# 74LVC8T245.net
KiCad netlist of a schematic drawn in Altium Designer
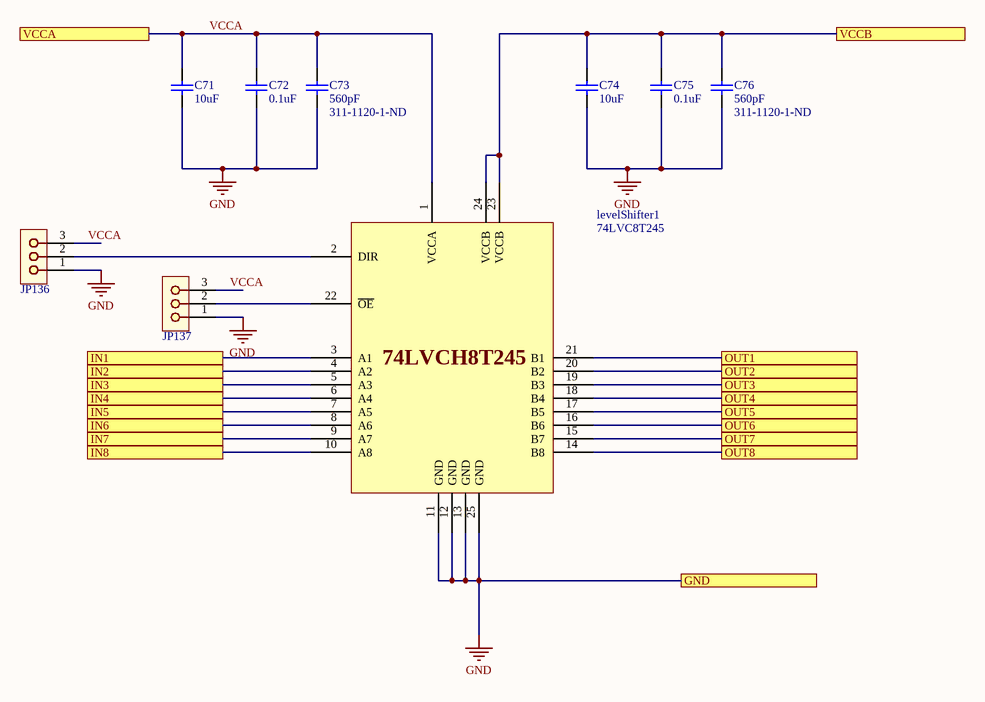
[diagram p0: 74LVC8T245.SchDoc]

(export (version "E")
  (design (tool "Eeschema 10.0.6"))
  (components
    (comp (ref "C71")
      (value "10uF")
      (footprint "CLS_Library:C0805")
      (description "Cap 10uF")
      (fields
        (field (name "MANUFACTURER") "Taiyo Yuden")
        (field (name "MANUFACTURER PART NUMBER") "UMK212SD103KD-T")
      )
      (libsource (lib "Chip1_TestBoard") (part "Cap 10uF"))
    )
    (comp (ref "C72")
      (value "0.1uF")
      (footprint "CLS_Library:C0805")
      (description "Cap 0.1uF")
      (fields
        (field (name "MANUFACTURER") "Taiyo Yuden")
        (field (name "MANUFACTURER PART NUMBER") "UMK212SD103KD-T")
      )
      (libsource (lib "Chip1_TestBoard") (part "Cap 0.1uF"))
    )
    (comp (ref "C73")
      (value "560pF")
      (footprint "CLS_Library:C0805")
      (description "Cap 560pF")
      (fields
        (field (name "MANUFACTURER") "Taiyo Yuden")
        (field (name "MANUFACTURER PART NUMBER") "UMK212SD103KD-T")
        (field (name "SUPPLIER PART NUMBER 1") "311-1120-1-ND")
      )
      (libsource (lib "Chip1_TestBoard") (part "Cap 560pF"))
    )
    (comp (ref "C74")
      (value "10uF")
      (footprint "CLS_Library:C0805")
      (description "Cap 10uF")
      (fields
        (field (name "MANUFACTURER") "Taiyo Yuden")
        (field (name "MANUFACTURER PART NUMBER") "UMK212SD103KD-T")
      )
      (libsource (lib "Chip1_TestBoard") (part "Cap 10uF"))
    )
    (comp (ref "C75")
      (value "0.1uF")
      (footprint "CLS_Library:C0805")
      (description "Cap 0.1uF")
      (fields
        (field (name "MANUFACTURER") "Taiyo Yuden")
        (field (name "MANUFACTURER PART NUMBER") "UMK212SD103KD-T")
      )
      (libsource (lib "Chip1_TestBoard") (part "Cap 0.1uF"))
    )
    (comp (ref "C76")
      (value "560pF")
      (footprint "CLS_Library:C0805")
      (description "Cap 560pF")
      (fields
        (field (name "MANUFACTURER") "Taiyo Yuden")
        (field (name "MANUFACTURER PART NUMBER") "UMK212SD103KD-T")
        (field (name "SUPPLIER PART NUMBER 1") "311-1120-1-ND")
      )
      (libsource (lib "Chip1_TestBoard") (part "Cap 560pF"))
    )
    (comp (ref "JP136")
      (value "01x03")
      (footprint "01x03_0.1in_th_straight_b_nom")
      (description "01X03 generic terminal connector")
      (libsource (lib "Chip1_TestBoard") (part "01x03"))
    )
    (comp (ref "JP137")
      (value "01x03")
      (footprint "01x03_0.1in_th_straight_b_nom")
      (description "01X03 generic terminal connector")
      (libsource (lib "Chip1_TestBoard") (part "01x03"))
    )
    (comp (ref "levelShifter1")
      (value "74LVC8T245")
      (footprint "Chip1_TestBoard:74LVCH8T245")
      (description "Bidirectional level shifter.")
      (libsource (lib "Chip1_TestBoard") (part "74LVC8T245"))
    )
  )
  (nets
    (net (code "1") (name "/IN1") (class "Default")
      (node (ref "levelShifter1") (pin "3") (pinfunction "A1_3") (pintype "passive"))
    )
    (net (code "2") (name "/IN2") (class "Default")
      (node (ref "levelShifter1") (pin "4") (pinfunction "A2_4") (pintype "passive"))
    )
    (net (code "3") (name "/IN3") (class "Default")
      (node (ref "levelShifter1") (pin "5") (pinfunction "A3_5") (pintype "passive"))
    )
    (net (code "4") (name "/IN4") (class "Default")
      (node (ref "levelShifter1") (pin "6") (pinfunction "A4_6") (pintype "passive"))
    )
    (net (code "5") (name "/IN5") (class "Default")
      (node (ref "levelShifter1") (pin "7") (pinfunction "A5_7") (pintype "passive"))
    )
    (net (code "6") (name "/IN6") (class "Default")
      (node (ref "levelShifter1") (pin "8") (pinfunction "A6_8") (pintype "passive"))
    )
    (net (code "7") (name "/IN7") (class "Default")
      (node (ref "levelShifter1") (pin "9") (pinfunction "A7_9") (pintype "passive"))
    )
    (net (code "8") (name "/IN8") (class "Default")
      (node (ref "levelShifter1") (pin "10") (pinfunction "A8_10") (pintype "passive"))
    )
    (net (code "9") (name "/OUT1") (class "Default")
      (node (ref "levelShifter1") (pin "21") (pinfunction "B1_21") (pintype "passive"))
    )
    (net (code "10") (name "/OUT2") (class "Default")
      (node (ref "levelShifter1") (pin "20") (pinfunction "B2_20") (pintype "passive"))
    )
    (net (code "11") (name "/OUT3") (class "Default")
      (node (ref "levelShifter1") (pin "19") (pinfunction "B3_19") (pintype "passive"))
    )
    (net (code "12") (name "/OUT4") (class "Default")
      (node (ref "levelShifter1") (pin "18") (pinfunction "B4_18") (pintype "passive"))
    )
    (net (code "13") (name "/OUT5") (class "Default")
      (node (ref "levelShifter1") (pin "17") (pinfunction "B5_17") (pintype "passive"))
    )
    (net (code "14") (name "/OUT6") (class "Default")
      (node (ref "levelShifter1") (pin "16") (pinfunction "B6_16") (pintype "passive"))
    )
    (net (code "15") (name "/OUT7") (class "Default")
      (node (ref "levelShifter1") (pin "15") (pinfunction "B7_15") (pintype "passive"))
    )
    (net (code "16") (name "/OUT8") (class "Default")
      (node (ref "levelShifter1") (pin "14") (pinfunction "B8_14") (pintype "passive"))
    )
    (net (code "17") (name "/VCCA") (class "Default")
      (node (ref "C71") (pin "2") (pinfunction "2_2") (pintype "passive"))
      (node (ref "C72") (pin "2") (pinfunction "2_2") (pintype "passive"))
      (node (ref "C73") (pin "2") (pinfunction "2_2") (pintype "passive"))
      (node (ref "JP136") (pin "3") (pinfunction "3_3") (pintype "passive"))
      (node (ref "JP137") (pin "3") (pinfunction "3_3") (pintype "passive"))
      (node (ref "levelShifter1") (pin "1") (pinfunction "VCCA_1") (pintype "passive"))
    )
    (net (code "18") (name "/VCCB") (class "Default")
      (node (ref "C74") (pin "2") (pinfunction "2_2") (pintype "passive"))
      (node (ref "C75") (pin "2") (pinfunction "2_2") (pintype "passive"))
      (node (ref "C76") (pin "2") (pinfunction "2_2") (pintype "passive"))
      (node (ref "levelShifter1") (pin "23") (pinfunction "VCCB_23") (pintype "passive"))
      (node (ref "levelShifter1") (pin "24") (pinfunction "VCCB_24") (pintype "passive"))
    )
    (net (code "19") (name "GND") (class "Default")
      (node (ref "C71") (pin "1") (pinfunction "1_1") (pintype "passive"))
      (node (ref "C72") (pin "1") (pinfunction "1_1") (pintype "passive"))
      (node (ref "C73") (pin "1") (pinfunction "1_1") (pintype "passive"))
      (node (ref "C74") (pin "1") (pinfunction "1_1") (pintype "passive"))
      (node (ref "C75") (pin "1") (pinfunction "1_1") (pintype "passive"))
      (node (ref "C76") (pin "1") (pinfunction "1_1") (pintype "passive"))
      (node (ref "JP136") (pin "1") (pinfunction "1_1") (pintype "passive"))
      (node (ref "JP137") (pin "1") (pinfunction "1_1") (pintype "passive"))
      (node (ref "levelShifter1") (pin "11") (pinfunction "GND_11") (pintype "passive"))
      (node (ref "levelShifter1") (pin "12") (pinfunction "GND_12") (pintype "passive"))
      (node (ref "levelShifter1") (pin "13") (pinfunction "GND_13") (pintype "passive"))
      (node (ref "levelShifter1") (pin "25") (pinfunction "GND_25") (pintype "passive"))
    )
    (net (code "20") (name "Net-(levelShifter1-DIR)") (class "Default")
      (node (ref "JP136") (pin "2") (pinfunction "2_2") (pintype "passive"))
      (node (ref "levelShifter1") (pin "2") (pinfunction "DIR_2") (pintype "passive"))
    )
    (net (code "21") (name "Net-(levelShifter1-~{OE})") (class "Default")
      (node (ref "JP137") (pin "2") (pinfunction "2_2") (pintype "passive"))
      (node (ref "levelShifter1") (pin "22") (pinfunction "~{OE}_22") (pintype "passive"))
    )
  )
)
